# SMD_Soldering_Board.net
KiCad netlist of a schematic drawn in EAGLE
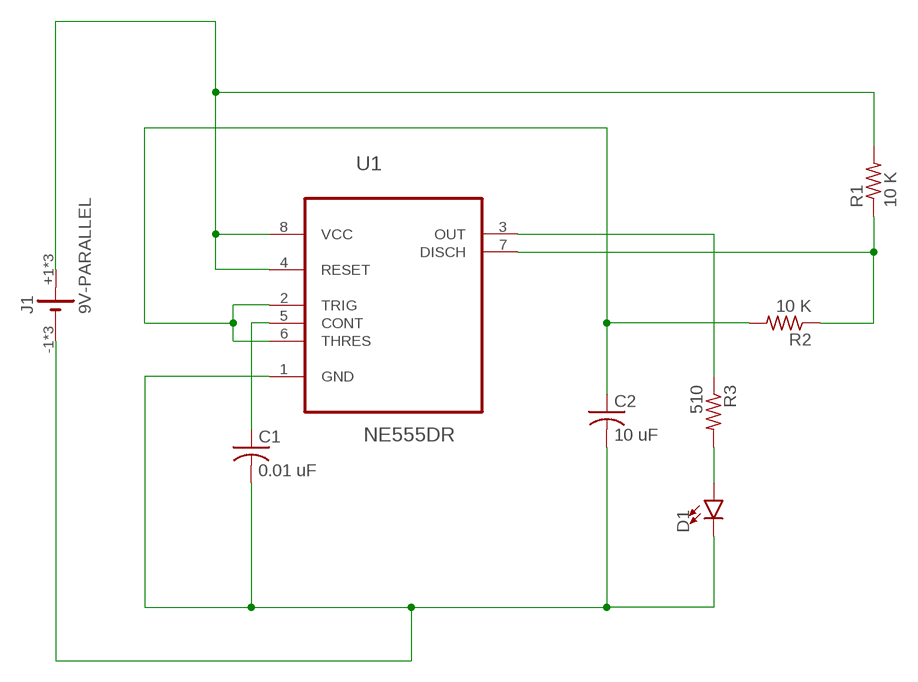
[diagram p0: schematic, sheet 1]

(export (version "E")
  (design (tool "Eeschema 10.0.6"))
  (components
    (comp (ref "C1")
      (value "0.01 uF")
      (footprint "eagle-import:C0603")
      (libsource (lib "eagle-import") (part "C-USC0603"))
    )
    (comp (ref "C2")
      (value "10 uF")
      (footprint "eagle-import:C0603")
      (libsource (lib "eagle-import") (part "C-USC0603"))
    )
    (comp (ref "D1")
      (value "LED0603")
      (footprint "eagle-import:LED-0603")
      (libsource (lib "eagle-import") (part "LED0603"))
    )
    (comp (ref "J1")
      (value "9V-PARALLEL")
      (footprint "eagle-import:9V-PARALLEL-CLIP")
      (libsource (lib "eagle-import") (part "9V-PARALLEL"))
    )
    (comp (ref "R1")
      (value "10 K")
      (footprint "eagle-import:R0603")
      (libsource (lib "eagle-import") (part "R-US_R0603"))
    )
    (comp (ref "R2")
      (value "10 K")
      (footprint "eagle-import:R0603")
      (libsource (lib "eagle-import") (part "R-US_R0603"))
    )
    (comp (ref "R3")
      (value "510")
      (footprint "eagle-import:R0603")
      (libsource (lib "eagle-import") (part "R-US_R0603"))
    )
    (comp (ref "U1")
      (value "NE555DR")
      (footprint "eagle-import:SOIC127P600X175-8N")
      (libsource (lib "eagle-import") (part "NE555DR"))
    )
  )
  (nets
    (net (code "1") (name "Net-(D1-PadA)") (class "Default")
      (node (ref "D1") (pin "A") (pinfunction "A_A") (pintype "passive"))
      (node (ref "R3") (pin "2") (pinfunction "2_2") (pintype "passive"))
    )
    (net (code "2") (name "Net-(U1-CONT)") (class "Default")
      (node (ref "C1") (pin "1") (pinfunction "1_1") (pintype "passive"))
      (node (ref "U1") (pin "5") (pinfunction "CONT_5") (pintype "input"))
    )
    (net (code "3") (name "Net-(U1-DISCH)") (class "Default")
      (node (ref "R1") (pin "1") (pinfunction "1_1") (pintype "passive"))
      (node (ref "R2") (pin "1") (pinfunction "1_1") (pintype "passive"))
      (node (ref "U1") (pin "7") (pinfunction "DISCH_7") (pintype "output"))
    )
    (net (code "4") (name "Net-(U1-GND)") (class "Default")
      (node (ref "C1") (pin "2") (pinfunction "2_2") (pintype "passive"))
      (node (ref "C2") (pin "2") (pinfunction "2_2") (pintype "passive"))
      (node (ref "D1") (pin "C") (pinfunction "C_C") (pintype "passive"))
      (node (ref "J1") (pin "-1") (pinfunction "-_-1") (pintype "passive"))
      (node (ref "J1") (pin "-2") (pinfunction "-_-2") (pintype "passive"))
      (node (ref "J1") (pin "-3") (pinfunction "-_-3") (pintype "passive"))
      (node (ref "U1") (pin "1") (pinfunction "GND_1") (pintype "passive"))
    )
    (net (code "5") (name "Net-(U1-OUT)") (class "Default")
      (node (ref "R3") (pin "1") (pinfunction "1_1") (pintype "passive"))
      (node (ref "U1") (pin "3") (pinfunction "OUT_3") (pintype "output"))
    )
    (net (code "6") (name "Net-(U1-RESET)") (class "Default")
      (node (ref "J1") (pin "+1") (pinfunction "+_+1") (pintype "passive"))
      (node (ref "J1") (pin "+2") (pinfunction "+_+2") (pintype "passive"))
      (node (ref "J1") (pin "+3") (pinfunction "+_+3") (pintype "passive"))
      (node (ref "R1") (pin "2") (pinfunction "2_2") (pintype "passive"))
      (node (ref "U1") (pin "4") (pinfunction "RESET_4") (pintype "input"))
      (node (ref "U1") (pin "8") (pinfunction "VCC_8") (pintype "power_in"))
    )
    (net (code "7") (name "Net-(U1-THRES)") (class "Default")
      (node (ref "C2") (pin "1") (pinfunction "1_1") (pintype "passive"))
      (node (ref "R2") (pin "2") (pinfunction "2_2") (pintype "passive"))
      (node (ref "U1") (pin "2") (pinfunction "TRIG_2") (pintype "input"))
      (node (ref "U1") (pin "6") (pinfunction "THRES_6") (pintype "input"))
    )
  )
)
